# ESP32.net
KiCad netlist of a schematic drawn in Altium Designer
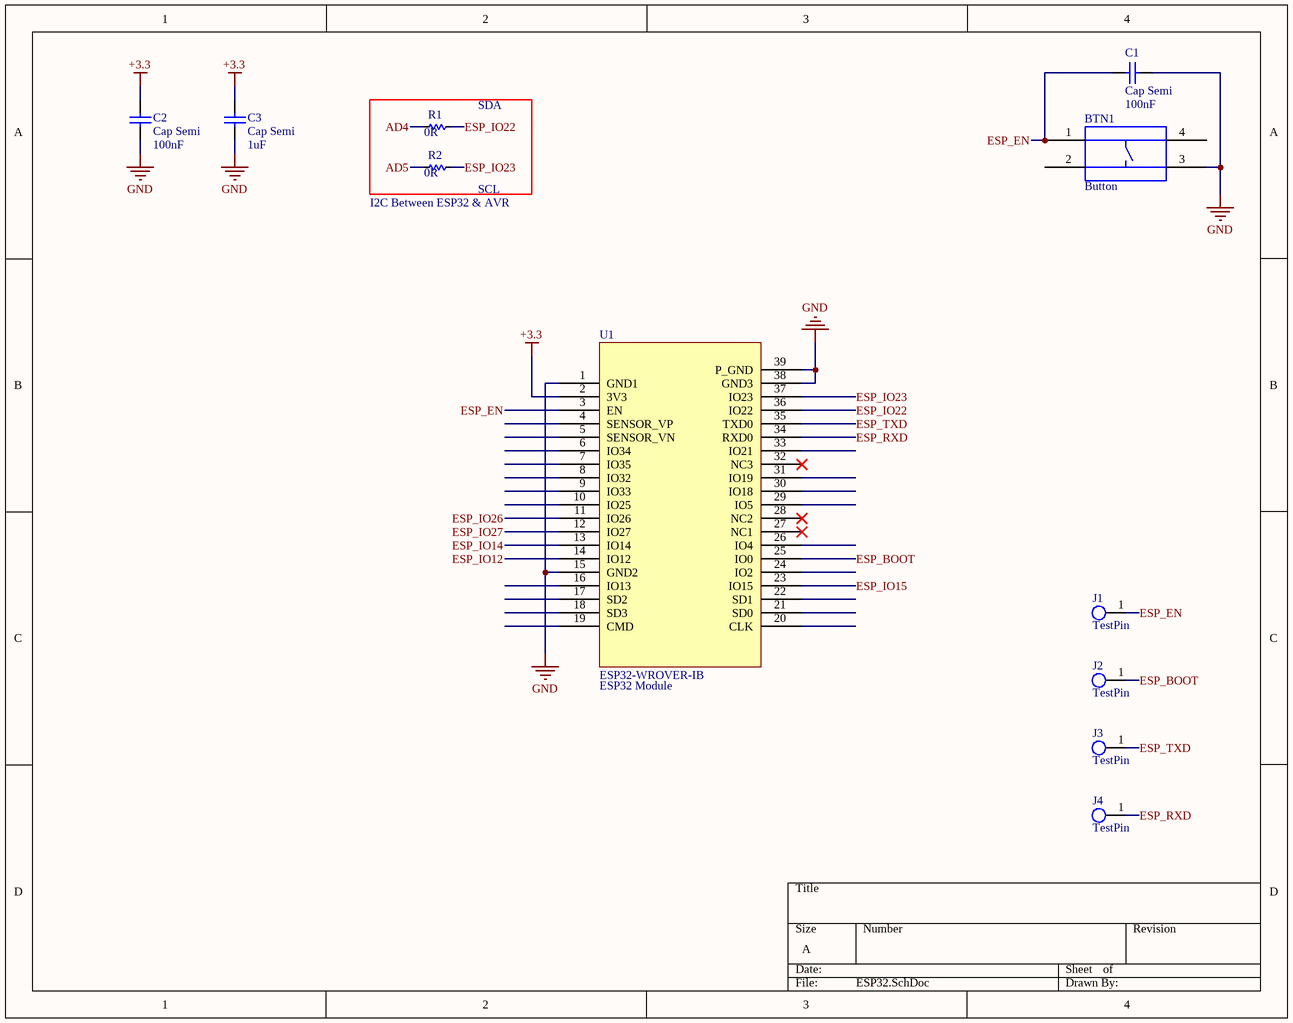
[diagram p0: ESP32.SchDoc]

(export (version "E")
  (design (tool "Eeschema 10.0.6"))
  (components
    (comp (ref "BTN1")
      (value "Button")
      (footprint "TactileButton_4x4")
      (libsource (lib "TactileButton_4x4") (part "Tactile_4x4"))
    )
    (comp (ref "C1")
      (value "Cap Semi")
      (footprint "1608[0603]")
      (description "Capacitor (Semiconductor SIM Model)")
      (fields (field (name "ALTIUM_VALUE") "100nF") (field (name "PUBLISHER") "Altium Limited"))
      (libsource (lib "Miscellaneous Devices") (part "Cap Semi"))
    )
    (comp (ref "C2")
      (value "Cap Semi")
      (footprint "1608[0603]")
      (description "Capacitor (Semiconductor SIM Model)")
      (fields (field (name "ALTIUM_VALUE") "100nF") (field (name "PUBLISHER") "Altium Limited"))
      (libsource (lib "Miscellaneous Devices") (part "Cap Semi"))
    )
    (comp (ref "C3")
      (value "Cap Semi")
      (footprint "1608[0603]")
      (description "Capacitor (Semiconductor SIM Model)")
      (fields (field (name "ALTIUM_VALUE") "1uF") (field (name "PUBLISHER") "Altium Limited"))
      (libsource (lib "Miscellaneous Devices") (part "Cap Semi"))
    )
    (comp (ref "J1")
      (value "TestPin")
      (footprint "TestPin_1mm")
      (description "Test conntact for pogo pins")
      (libsource (lib "TestPin") (part "TestPin_1mm"))
    )
    (comp (ref "J2")
      (value "TestPin")
      (footprint "TestPin_1mm")
      (description "Test conntact for pogo pins")
      (libsource (lib "TestPin") (part "TestPin_1mm"))
    )
    (comp (ref "J3")
      (value "TestPin")
      (footprint "TestPin_1mm")
      (description "Test conntact for pogo pins")
      (libsource (lib "TestPin") (part "TestPin_1mm"))
    )
    (comp (ref "J4")
      (value "TestPin")
      (footprint "TestPin_1mm")
      (description "Test conntact for pogo pins")
      (libsource (lib "TestPin") (part "TestPin_1mm"))
    )
    (comp (ref "R1")
      (value "0R")
      (footprint "RES-SMD-0603")
      (description "Resistor")
      (fields
        (field (name "MANUFACTURER") "Generic Components")
        (field (name "Comment") "Res")
        (field (name "PUBLISHER") "Altium Hobart Technology Centre")
      )
      (libsource (lib "LIBRARY") (part "Res-SMD"))
    )
    (comp (ref "R2")
      (value "0R")
      (footprint "RES-SMD-0603")
      (description "Resistor")
      (fields
        (field (name "MANUFACTURER") "Generic Components")
        (field (name "Comment") "Res")
        (field (name "PUBLISHER") "Altium Hobart Technology Centre")
      )
      (libsource (lib "LIBRARY") (part "Res-SMD"))
    )
    (comp (ref "U1")
      (value "ESP32 Module")
      (footprint "ESP32-WROVER-IB")
      (fields (field (name "MANUFACTURER") "Espressif Systems"))
      (libsource (lib "ESP32-WROVER-IB") (part "ESP32-WROVER-IB"))
    )
  )
  (nets
    (net (code "1") (name "+3.3") (class "Default")
      (node (ref "C2") (pin "2") (pinfunction "2_2") (pintype "passive"))
      (node (ref "C3") (pin "2") (pinfunction "2_2") (pintype "passive"))
      (node (ref "U1") (pin "2") (pinfunction "3V3_2") (pintype "passive"))
    )
    (net (code "2") (name "/AD4") (class "Default")
      (node (ref "R1") (pin "2") (pinfunction "2_2") (pintype "passive"))
    )
    (net (code "3") (name "/AD5") (class "Default")
      (node (ref "R2") (pin "2") (pinfunction "2_2") (pintype "passive"))
    )
    (net (code "4") (name "/ESP_BOOT") (class "Default")
      (node (ref "J2") (pin "1") (pinfunction "1_1") (pintype "passive"))
      (node (ref "U1") (pin "25") (pinfunction "IO0_25") (pintype "passive"))
    )
    (net (code "5") (name "/ESP_EN") (class "Default")
      (node (ref "BTN1") (pin "1") (pinfunction "Pin1_1") (pintype "passive"))
      (node (ref "C1") (pin "2") (pinfunction "2_2") (pintype "passive"))
      (node (ref "J1") (pin "1") (pinfunction "1_1") (pintype "passive"))
      (node (ref "U1") (pin "3") (pinfunction "EN_3") (pintype "passive"))
    )
    (net (code "6") (name "/ESP_IO12") (class "Default")
      (node (ref "U1") (pin "14") (pinfunction "IO12_14") (pintype "passive"))
    )
    (net (code "7") (name "/ESP_IO14") (class "Default")
      (node (ref "U1") (pin "13") (pinfunction "IO14_13") (pintype "passive"))
    )
    (net (code "8") (name "/ESP_IO15") (class "Default")
      (node (ref "U1") (pin "23") (pinfunction "IO15_23") (pintype "passive"))
    )
    (net (code "9") (name "/ESP_IO22") (class "Default")
      (node (ref "R1") (pin "1") (pinfunction "1_1") (pintype "passive"))
      (node (ref "U1") (pin "36") (pinfunction "IO22_36") (pintype "passive"))
    )
    (net (code "10") (name "/ESP_IO23") (class "Default")
      (node (ref "R2") (pin "1") (pinfunction "1_1") (pintype "passive"))
      (node (ref "U1") (pin "37") (pinfunction "IO23_37") (pintype "passive"))
    )
    (net (code "11") (name "/ESP_IO26") (class "Default")
      (node (ref "U1") (pin "11") (pinfunction "IO26_11") (pintype "passive"))
    )
    (net (code "12") (name "/ESP_IO27") (class "Default")
      (node (ref "U1") (pin "12") (pinfunction "IO27_12") (pintype "passive"))
    )
    (net (code "13") (name "/ESP_RXD") (class "Default")
      (node (ref "J4") (pin "1") (pinfunction "1_1") (pintype "passive"))
      (node (ref "U1") (pin "34") (pinfunction "RXD0_34") (pintype "passive"))
    )
    (net (code "14") (name "/ESP_TXD") (class "Default")
      (node (ref "J3") (pin "1") (pinfunction "1_1") (pintype "passive"))
      (node (ref "U1") (pin "35") (pinfunction "TXD0_35") (pintype "passive"))
    )
    (net (code "15") (name "GND") (class "Default")
      (node (ref "BTN1") (pin "3") (pinfunction "Pin3_3") (pintype "passive"))
      (node (ref "C1") (pin "1") (pinfunction "1_1") (pintype "passive"))
      (node (ref "C2") (pin "1") (pinfunction "1_1") (pintype "passive"))
      (node (ref "C3") (pin "1") (pinfunction "1_1") (pintype "passive"))
      (node (ref "U1") (pin "1") (pinfunction "GND1_1") (pintype "passive"))
      (node (ref "U1") (pin "15") (pinfunction "GND2_15") (pintype "passive"))
      (node (ref "U1") (pin "38") (pinfunction "GND3_38") (pintype "passive"))
      (node (ref "U1") (pin "39") (pinfunction "P_GND_39") (pintype "passive"))
    )
    (net (code "16") (name "unconnected-(BTN1-Pin2-Pad2)") (class "Default")
      (node (ref "BTN1") (pin "2") (pinfunction "Pin2_2") (pintype "passive"))
    )
    (net (code "17") (name "unconnected-(BTN1-Pin4-Pad4)") (class "Default")
      (node (ref "BTN1") (pin "4") (pinfunction "Pin4_4") (pintype "passive"))
    )
    (net (code "18") (name "unconnected-(U1-CLK-Pad20)") (class "Default")
      (node (ref "U1") (pin "20") (pinfunction "CLK_20") (pintype "passive"))
    )
    (net (code "19") (name "unconnected-(U1-CMD-Pad19)") (class "Default")
      (node (ref "U1") (pin "19") (pinfunction "CMD_19") (pintype "passive"))
    )
    (net (code "20") (name "unconnected-(U1-IO2-Pad24)") (class "Default")
      (node (ref "U1") (pin "24") (pinfunction "IO2_24") (pintype "passive"))
    )
    (net (code "21") (name "unconnected-(U1-IO4-Pad26)") (class "Default")
      (node (ref "U1") (pin "26") (pinfunction "IO4_26") (pintype "passive"))
    )
    (net (code "22") (name "unconnected-(U1-IO5-Pad29)") (class "Default")
      (node (ref "U1") (pin "29") (pinfunction "IO5_29") (pintype "passive"))
    )
    (net (code "23") (name "unconnected-(U1-IO13-Pad16)") (class "Default")
      (node (ref "U1") (pin "16") (pinfunction "IO13_16") (pintype "passive"))
    )
    (net (code "24") (name "unconnected-(U1-IO18-Pad30)") (class "Default")
      (node (ref "U1") (pin "30") (pinfunction "IO18_30") (pintype "passive"))
    )
    (net (code "25") (name "unconnected-(U1-IO19-Pad31)") (class "Default")
      (node (ref "U1") (pin "31") (pinfunction "IO19_31") (pintype "passive"))
    )
    (net (code "26") (name "unconnected-(U1-IO21-Pad33)") (class "Default")
      (node (ref "U1") (pin "33") (pinfunction "IO21_33") (pintype "passive"))
    )
    (net (code "27") (name "unconnected-(U1-IO25-Pad10)") (class "Default")
      (node (ref "U1") (pin "10") (pinfunction "IO25_10") (pintype "passive"))
    )
    (net (code "28") (name "unconnected-(U1-IO32-Pad8)") (class "Default")
      (node (ref "U1") (pin "8") (pinfunction "IO32_8") (pintype "passive"))
    )
    (net (code "29") (name "unconnected-(U1-IO33-Pad9)") (class "Default")
      (node (ref "U1") (pin "9") (pinfunction "IO33_9") (pintype "passive"))
    )
    (net (code "30") (name "unconnected-(U1-IO34-Pad6)") (class "Default")
      (node (ref "U1") (pin "6") (pinfunction "IO34_6") (pintype "passive"))
    )
    (net (code "31") (name "unconnected-(U1-IO35-Pad7)") (class "Default")
      (node (ref "U1") (pin "7") (pinfunction "IO35_7") (pintype "passive"))
    )
    (net (code "32") (name "unconnected-(U1-NC1-Pad27)") (class "Default")
      (node (ref "U1") (pin "27") (pinfunction "NC1_27") (pintype "passive+no_connect"))
    )
    (net (code "33") (name "unconnected-(U1-NC2-Pad28)") (class "Default")
      (node (ref "U1") (pin "28") (pinfunction "NC2_28") (pintype "passive+no_connect"))
    )
    (net (code "34") (name "unconnected-(U1-NC3-Pad32)") (class "Default")
      (node (ref "U1") (pin "32") (pinfunction "NC3_32") (pintype "passive+no_connect"))
    )
    (net (code "35") (name "unconnected-(U1-SD0-Pad21)") (class "Default")
      (node (ref "U1") (pin "21") (pinfunction "SD0_21") (pintype "passive"))
    )
    (net (code "36") (name "unconnected-(U1-SD1-Pad22)") (class "Default")
      (node (ref "U1") (pin "22") (pinfunction "SD1_22") (pintype "passive"))
    )
    (net (code "37") (name "unconnected-(U1-SD2-Pad17)") (class "Default")
      (node (ref "U1") (pin "17") (pinfunction "SD2_17") (pintype "passive"))
    )
    (net (code "38") (name "unconnected-(U1-SD3-Pad18)") (class "Default")
      (node (ref "U1") (pin "18") (pinfunction "SD3_18") (pintype "passive"))
    )
    (net (code "39") (name "unconnected-(U1-SENSOR_VN-Pad5)") (class "Default")
      (node (ref "U1") (pin "5") (pinfunction "SENSOR_VN_5") (pintype "passive"))
    )
    (net (code "40") (name "unconnected-(U1-SENSOR_VP-Pad4)") (class "Default")
      (node (ref "U1") (pin "4") (pinfunction "SENSOR_VP_4") (pintype "passive"))
    )
  )
)
